# 13_USB30_USB20.net
KiCad netlist of a schematic drawn in Altium Designer
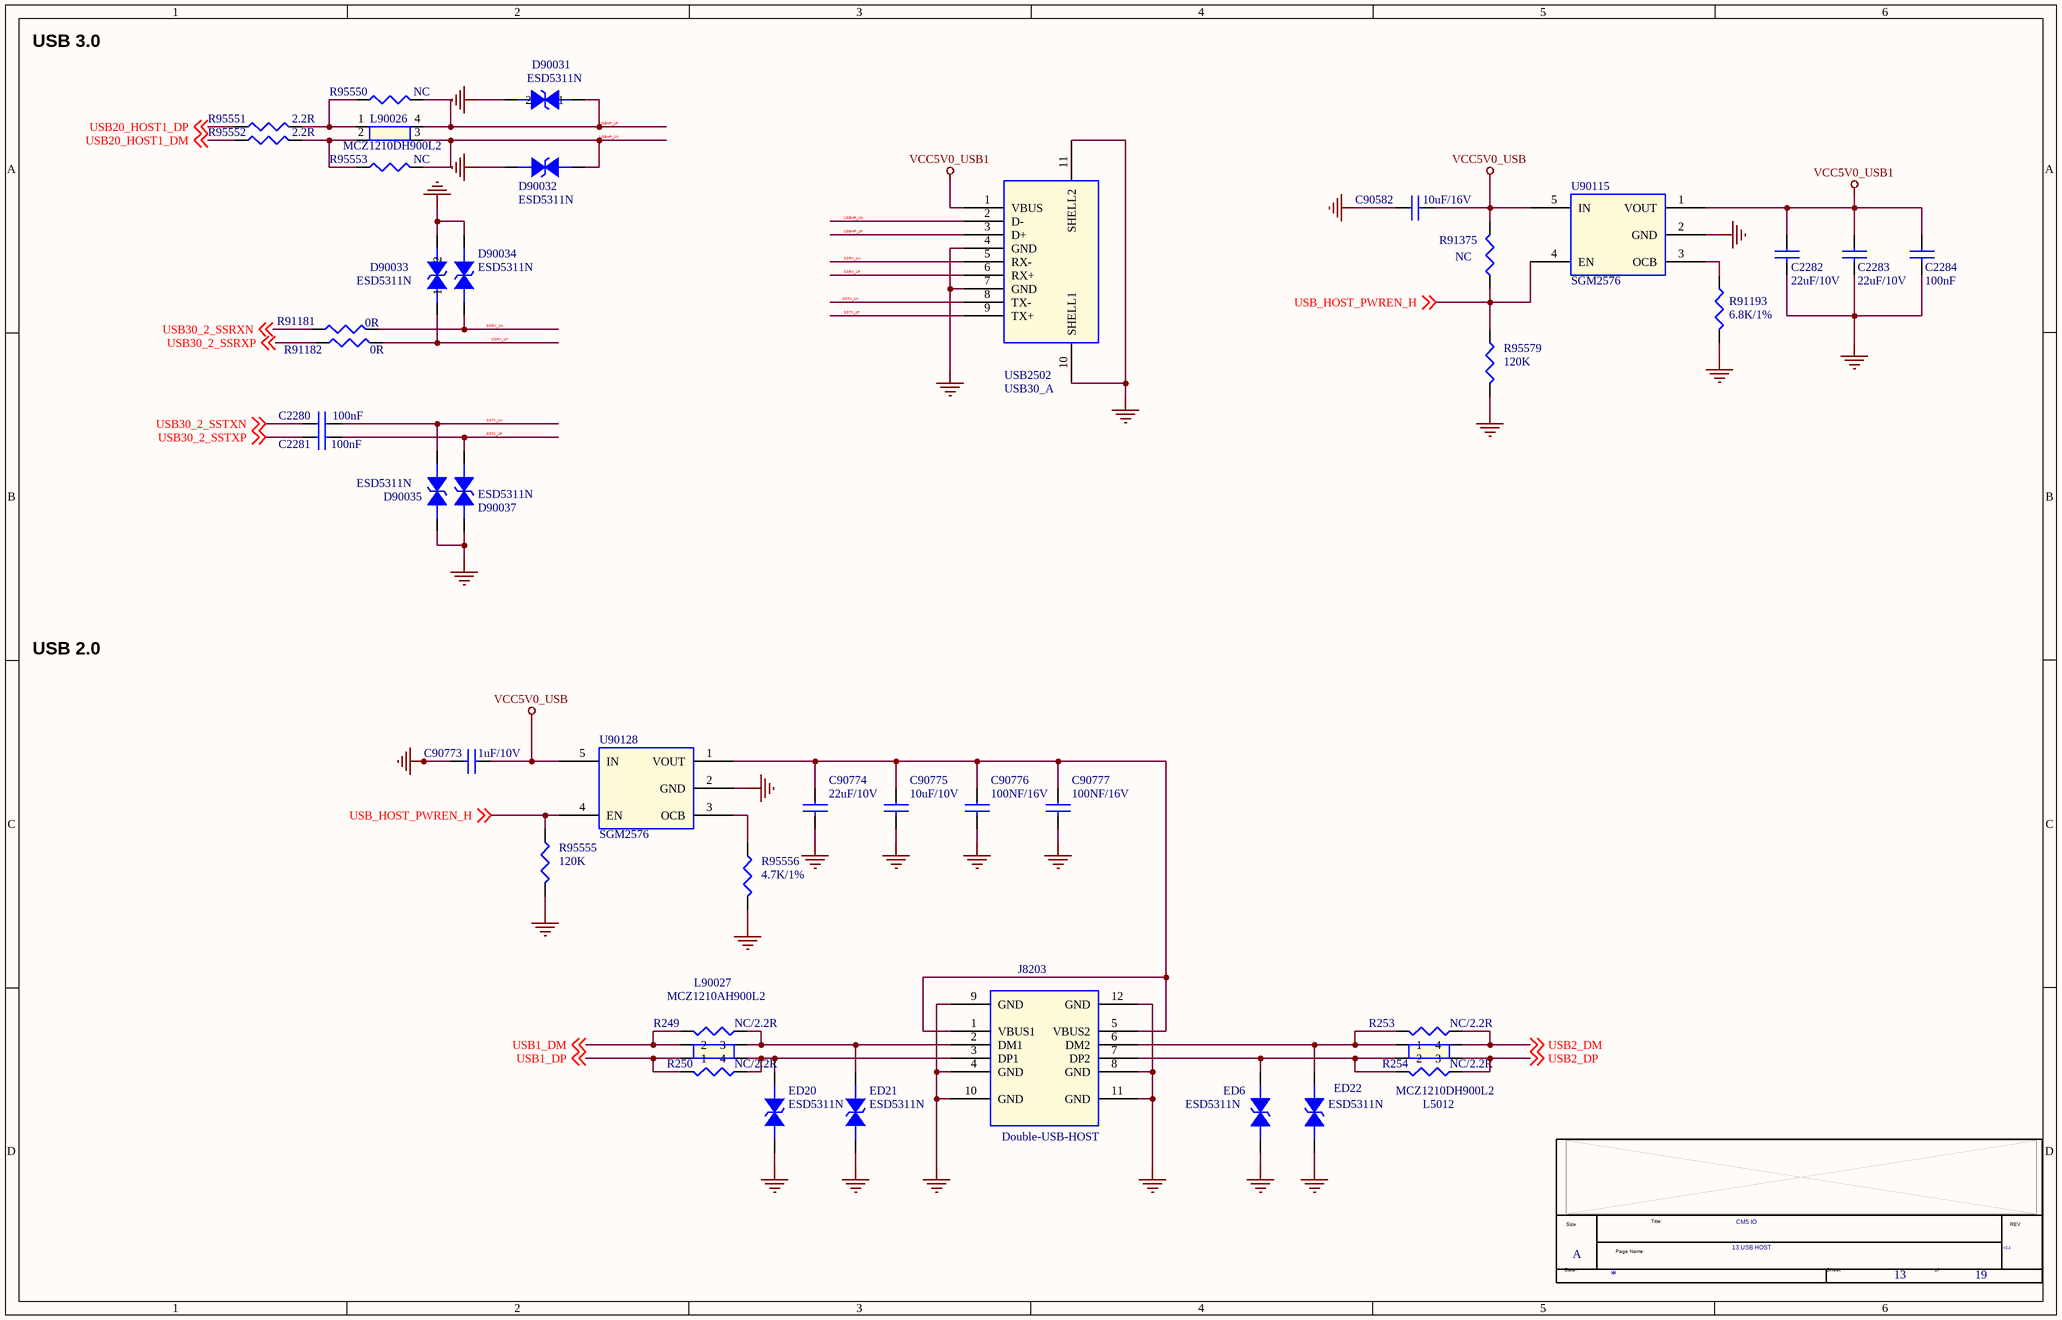
[diagram p0: 13_USB30_USB20.SchDoc]

(export (version "E")
  (design (tool "Eeschema 10.0.6"))
  (components
    (comp (ref "*")
      (value "radxa_1010")
      (fields
        (field (name "DOC") "13.USB HOST")
        (field (name "REVCODE") "V2.2")
        (field (name "TITLE") "CM5 IO")
        (field (name "PAGE SIZE") "A")
        (field (name "PAGE NUMBER") "13")
        (field (name "PAGE COUNT") "19")
      )
      (libsource (lib "*") (part "radxa_1010"))
    )
    (comp (ref "C2280")
      (value "100nF")
      (footprint "C0201")
      (description "cap,100.00nF,+/-10%,10V,X5R,C0201")
      (fields
        (field (name "VOLTAGE") "10V")
        (field (name "MANUFACTURER") "TDK")
        (field (name "CREATED BY") "JJJ")
      )
      (libsource (lib "*") (part "CAP NP_0_Dup1"))
    )
    (comp (ref "C2281")
      (value "100nF")
      (footprint "C0201")
      (description "cap,100.00nF,+/-10%,10V,X5R,C0201")
      (fields
        (field (name "VOLTAGE") "10V")
        (field (name "TOLERANCE") "10%")
        (field (name "CREATED BY") "JJJ")
      )
      (libsource (lib "*") (part "CAP NP_0_Dup1"))
    )
    (comp (ref "C2282")
      (value "22uF/10V")
      (footprint "C0603")
      (description "cap,100.00nF,+/-10%,10V,X5R,C0402")
      (fields
        (field (name "VOLTAGE") "10V")
        (field (name "TOLERANCE") "10%")
        (field (name "CREATED BY") "JJJ")
      )
      (libsource (lib "*") (part "CAP NP_0_Dup1"))
    )
    (comp (ref "C2283")
      (value "22uF/10V")
      (footprint "C0603")
      (description "cap,100.00nF,+/-10%,10V,X5R,C0402")
      (fields
        (field (name "VOLTAGE") "10V")
        (field (name "MANUFACTURER") "TDK")
        (field (name "CREATED BY") "JJJ")
      )
      (libsource (lib "*") (part "CAP NP_0_Dup1"))
    )
    (comp (ref "C2284")
      (value "100nF")
      (footprint "C0201")
      (description "cap,100.00nF,+/-10%,10V,X5R,C0402")
      (fields
        (field (name "VOLTAGE") "10V")
        (field (name "MANUFACTURER") "TDK")
        (field (name "CREATED BY") "JJJ")
      )
      (libsource (lib "*") (part "CAP NP_0_Dup1"))
    )
    (comp (ref "C90582")
      (value "10uF/16V")
      (footprint "C0402")
      (description "0402 ∮20% 10uF X5R 6.3V")
      (libsource (lib "*") (part "C / 10 / uF / 0402_0"))
    )
    (comp (ref "C90773")
      (value "1uF/10V")
      (footprint "C0402")
      (description "cap,1.00uF,+/-10%,10V,X5R,C0402")
      (fields
        (field (name "VOLTAGE") "10V")
        (field (name "MANUFACTURER") "TDK")
        (field (name "CREATED BY") "JJJ")
      )
      (libsource (lib "*") (part "CAP NP_0_Dup2"))
    )
    (comp (ref "C90774")
      (value "22uF/10V")
      (footprint "C0603")
      (description "cap,22.00uF,+/-20%,10V,X5R,C0603")
      (fields
        (field (name "VOLTAGE") "10V")
        (field (name "MANUFACTURER") "TDK")
        (field (name "CREATED BY") "JJJ")
      )
      (libsource (lib "*") (part "CAP NP_0_Dup2"))
    )
    (comp (ref "C90775")
      (value "10uF/10V")
      (footprint "C0603")
      (description "cap,10.00uF,+/-10%,10V,X5R,C0603")
      (fields
        (field (name "VOLTAGE") "10V")
        (field (name "TOLERANCE") "10%")
        (field (name "CREATED BY") "JJJ")
      )
      (libsource (lib "*") (part "CAP NP_0_Dup2"))
    )
    (comp (ref "C90776")
      (value "100NF/16V")
      (footprint "C0402")
      (description "cap,100.00nF,+/-10%,16V,X5R,C0402")
      (fields
        (field (name "VOLTAGE") "16V")
        (field (name "TOLERANCE") "10%")
        (field (name "CREATED BY") "JJJ")
      )
      (libsource (lib "*") (part "CAP NP_0_Dup2"))
    )
    (comp (ref "C90777")
      (value "100NF/16V")
      (footprint "C0402")
      (description "cap,100.00nF,+/-10%,16V,X5R,C0402")
      (fields
        (field (name "VOLTAGE") "16V")
        (field (name "TOLERANCE") "10%")
        (field (name "CREATED BY") "JJJ")
      )
      (libsource (lib "*") (part "CAP NP_0_Dup2"))
    )
    (comp (ref "D90031")
      (value "ESD5311N")
      (footprint "ESD0402")
      (description "1-Line, Bi-directional, Transient Voltage Suppressors.1pF.")
      (fields (field (name "MANUFACTURER") "WillSemi(韦尔半导体)") (field (name "CREATED BY") "JJJ"))
      (libsource (lib "*") (part "DIODE BI_DIR TRIG_0"))
    )
    (comp (ref "D90032")
      (value "ESD5311N")
      (footprint "ESD0402")
      (description "1-Line, Bi-directional, Transient Voltage Suppressors.1pF.")
      (fields (field (name "MANUFACTURER") "WillSemi(韦尔半导体)") (field (name "CREATED BY") "JJJ"))
      (libsource (lib "*") (part "DIODE BI_DIR TRIG_1_Dup1"))
    )
    (comp (ref "D90033")
      (value "ESD5311N")
      (footprint "ESD0402")
      (description "1-Line, Bi-directional, Transient Voltage Suppressors.1pF.")
      (fields (field (name "MANUFACTURER") "WillSemi(韦尔半导体)") (field (name "CREATED BY") "JJJ"))
      (libsource (lib "*") (part "DIODE BI_DIR TRIG_1"))
    )
    (comp (ref "D90034")
      (value "ESD5311N")
      (footprint "ESD0402")
      (description "1-Line, Bi-directional, Transient Voltage Suppressors.1pF.")
      (fields (field (name "MANUFACTURER") "WillSemi(韦尔半导体)") (field (name "CREATED BY") "JJJ"))
      (libsource (lib "*") (part "DIODE BI_DIR TRIG_1_Dup1"))
    )
    (comp (ref "D90035")
      (value "ESD5311N")
      (footprint "ESD0402")
      (description "1-Line, Bi-directional, Transient Voltage Suppressors.1pF.")
      (fields (field (name "MANUFACTURER") "WillSemi(韦尔半导体)") (field (name "CREATED BY") "JJJ"))
      (libsource (lib "*") (part "DIODE BI_DIR TRIG_1_Dup1"))
    )
    (comp (ref "D90037")
      (value "ESD5311N")
      (footprint "ESD0402")
      (description "1-Line, Bi-directional, Transient Voltage Suppressors.1pF.")
      (fields (field (name "MANUFACTURER") "WillSemi(韦尔半导体)") (field (name "CREATED BY") "JJJ"))
      (libsource (lib "*") (part "DIODE BI_DIR TRIG_1_Dup1"))
    )
    (comp (ref "ED6")
      (value "ESD5311N")
      (footprint "ESD0402")
      (description "1-Line, Bi-directional, Transient Voltage Suppressors.1pF.")
      (fields (field (name "MANUFACTURER") "WillSemi(韦尔半导体)") (field (name "CREATED BY") "JJJ"))
      (libsource (lib "*") (part "DIODE BI_DIR TRIG_1_Dup1"))
    )
    (comp (ref "ED20")
      (value "ESD5311N")
      (footprint "ESD0402")
      (description "1-Line, Bi-directional, Transient Voltage Suppressors.1pF.")
      (fields (field (name "MANUFACTURER") "WillSemi(韦尔半导体)") (field (name "CREATED BY") "JJJ"))
      (libsource (lib "*") (part "DIODE BI_DIR TRIG_1_Dup1"))
    )
    (comp (ref "ED21")
      (value "ESD5311N")
      (footprint "ESD0402")
      (description "1-Line, Bi-directional, Transient Voltage Suppressors.1pF.")
      (fields (field (name "MANUFACTURER") "WillSemi(韦尔半导体)") (field (name "CREATED BY") "JJJ"))
      (libsource (lib "*") (part "DIODE BI_DIR TRIG_1_Dup1"))
    )
    (comp (ref "ED22")
      (value "ESD5311N")
      (footprint "ESD0402")
      (description "1-Line, Bi-directional, Transient Voltage Suppressors.1pF.")
      (fields (field (name "MANUFACTURER") "WillSemi(韦尔半导体)") (field (name "CREATED BY") "JJJ"))
      (libsource (lib "*") (part "DIODE BI_DIR TRIG_1_Dup1"))
    )
    (comp (ref "J8203")
      (value "Double-USB-HOST")
      (footprint "USB_DUAL")
      (libsource (lib "*") (part "Double-USB"))
    )
    (comp (ref "L5012")
      (value "MCZ1210DH900L2")
      (footprint "MCZ1210AH900L2")
      (libsource (lib "*") (part "MCZ1210AH900L2_3"))
    )
    (comp (ref "L90026")
      (value "MCZ1210DH900L2")
      (footprint "MCZ1210AH900L2")
      (libsource (lib "*") (part "MCZ1210AH900L2_1_Dup1"))
    )
    (comp (ref "L90027")
      (value "MCZ1210AH900L2")
      (footprint "MCZ1210AH900L2")
      (libsource (lib "") (part "MCZ1210AH900L2_3_1"))
    )
    (comp (ref "R249")
      (value "NC/2.2R")
      (footprint "R0402")
      (description "通用厚膜电阻,2R2,+/-5%,R0402,1/16W.")
      (fields
        (field (name "TOLERANCE") "5%")
        (field (name "MANUFACTURER") "YAGEO")
        (field (name "CREATED BY") "YTL")
      )
      (libsource (lib "*") (part "RESISTOR_1_Dup1"))
    )
    (comp (ref "R250")
      (value "NC/2.2R")
      (footprint "R0402")
      (description "通用厚膜电阻,2R2,+/-5%,R0402,1/16W.")
      (fields
        (field (name "TOLERANCE") "5%")
        (field (name "MANUFACTURER") "YAGEO")
        (field (name "CREATED BY") "YTL")
      )
      (libsource (lib "*") (part "RESISTOR_1_Dup1"))
    )
    (comp (ref "R253")
      (value "NC/2.2R")
      (footprint "R0402")
      (description "通用厚膜电阻,2R2,+/-5%,R0402,1/16W.")
      (fields
        (field (name "TOLERANCE") "5%")
        (field (name "MANUFACTURER") "YAGEO")
        (field (name "CREATED BY") "YTL")
      )
      (libsource (lib "*") (part "RESISTOR_1_Dup1"))
    )
    (comp (ref "R254")
      (value "NC/2.2R")
      (footprint "R0402")
      (description "通用厚膜电阻,2R2,+/-5%,R0402,1/16W.")
      (fields
        (field (name "TOLERANCE") "5%")
        (field (name "MANUFACTURER") "YAGEO")
        (field (name "CREATED BY") "YTL")
      )
      (libsource (lib "*") (part "RESISTOR_1_Dup1"))
    )
    (comp (ref "R91181")
      (value "0R")
      (footprint "R0402")
      (description "通用厚膜电阻,0R,+/-5%,R0201,1/20W.")
      (fields
        (field (name "TOLERANCE") "5%")
        (field (name "MANUFACTURER") "YAGEO")
        (field (name "CREATED BY") "YTL")
      )
      (libsource (lib "*") (part "RESISTOR_0_Dup1"))
    )
    (comp (ref "R91182")
      (value "0R")
      (footprint "R0402")
      (description "通用厚膜电阻,0R,+/-5%,R0201,1/20W.")
      (fields
        (field (name "TOLERANCE") "5%")
        (field (name "MANUFACTURER") "YAGEO")
        (field (name "CREATED BY") "YTL")
      )
      (libsource (lib "*") (part "RESISTOR_0_Dup1"))
    )
    (comp (ref "R91193")
      (value "6.8K/1%")
      (footprint "R0402")
      (description "通用厚膜电阻,4K7,+/-5%,R0402,1/16W.")
      (fields
        (field (name "TOLERANCE") "1%")
        (field (name "MANUFACTURER") "YAGEO")
        (field (name "CREATED BY") "YTL")
      )
      (libsource (lib "*") (part "RESISTOR_0_Dup1"))
    )
    (comp (ref "R91375")
      (value "NC")
      (footprint "R0402")
      (description "Did Not Place.")
      (fields (field (name "TOLERANCE") "0%") (field (name "CREATED BY") "JJJ"))
      (libsource (lib "*") (part "RESISTOR_0_Dup1"))
    )
    (comp (ref "R95550")
      (value "NC")
      (footprint "R0402")
      (description "通用厚膜电阻,2R2,+/-5%,R0402,1/16W.")
      (fields
        (field (name "TOLERANCE") "5%")
        (field (name "MANUFACTURER") "YAGEO")
        (field (name "CREATED BY") "YTL")
      )
      (libsource (lib "*") (part "RESISTOR_0_Dup1"))
    )
    (comp (ref "R95551")
      (value "2.2R")
      (footprint "R0402")
      (description "通用厚膜电阻,2R2,+/-5%,R0402,1/16W.")
      (fields
        (field (name "TOLERANCE") "5%")
        (field (name "MANUFACTURER") "YAGEO")
        (field (name "CREATED BY") "YTL")
      )
      (libsource (lib "*") (part "RESISTOR_0_Dup1"))
    )
    (comp (ref "R95552")
      (value "2.2R")
      (footprint "R0402")
      (description "通用厚膜电阻,2R2,+/-5%,R0402,1/16W.")
      (fields
        (field (name "TOLERANCE") "5%")
        (field (name "MANUFACTURER") "YAGEO")
        (field (name "CREATED BY") "YTL")
      )
      (libsource (lib "*") (part "RESISTOR_0_Dup1"))
    )
    (comp (ref "R95553")
      (value "NC")
      (footprint "R0402")
      (description "通用厚膜电阻,2R2,+/-5%,R0402,1/16W.")
      (fields
        (field (name "TOLERANCE") "5%")
        (field (name "MANUFACTURER") "YAGEO")
        (field (name "CREATED BY") "YTL")
      )
      (libsource (lib "*") (part "RESISTOR_0_Dup1"))
    )
    (comp (ref "R95555")
      (value "120K")
      (footprint "R0402")
      (description "通用厚膜电阻,100K,+/-5%,R0402,1/16W.")
      (fields
        (field (name "TOLERANCE") "5%")
        (field (name "MANUFACTURER") "YAGEO")
        (field (name "CREATED BY") "YTL")
      )
      (libsource (lib "*") (part "RESISTOR_1_Dup1"))
    )
    (comp (ref "R95556")
      (value "4.7K/1%")
      (footprint "R0402")
      (description "通用厚膜电阻,10K,+/-1%,R0402,1/16W.")
      (fields
        (field (name "TOLERANCE") "1%")
        (field (name "MANUFACTURER") "YAGEO")
        (field (name "CREATED BY") "YTL")
      )
      (libsource (lib "*") (part "RESISTOR_1_Dup1"))
    )
    (comp (ref "R95579")
      (value "120K")
      (footprint "R0402")
      (description "通用厚膜电阻,100K,+/-5%,R0402,1/16W.")
      (fields
        (field (name "TOLERANCE") "5%")
        (field (name "MANUFACTURER") "YAGEO")
        (field (name "CREATED BY") "YTL")
      )
      (libsource (lib "*") (part "RESISTOR_1_Dup1"))
    )
    (comp (ref "U90115")
      (value "SGM2576")
      (footprint "SOT_23_5")
      (description "Low Loss Power Distribution Switch")
      (fields (field (name "MANUFACTURER") "Silergy（矽力杰）") (field (name "CREATED BY") "JJJ"))
      (libsource (lib "*") (part "SWITCH_SY6280"))
    )
    (comp (ref "U90128")
      (value "SGM2576")
      (footprint "SOT_23_5")
      (description "Low Loss Power Distribution Switch")
      (fields (field (name "MANUFACTURER") "Silergy（矽力杰）") (field (name "CREATED BY") "JJJ"))
      (libsource (lib "*") (part "SWITCH_SY6280"))
    )
    (comp (ref "USB2502")
      (value "USB30_A")
      (footprint "USB30")
      (description "A型USB3.0座，卧式，插焊")
      (fields (field (name "MANUFACTURER") "旺科达") (field (name "CREATED BY") "JJJ"))
      (libsource (lib "*") (part "USB30_TYPE_A"))
    )
  )
  (nets
    (net (code "1") (name "/SSRX_1N") (class "Default")
      (node (ref "D90034") (pin "1") (pinfunction "1_1") (pintype "passive"))
      (node (ref "R91181") (pin "2") (pinfunction "2_2") (pintype "passive"))
      (node (ref "USB2502") (pin "5") (pinfunction "RX-_5") (pintype "passive"))
    )
    (net (code "2") (name "/SSRX_1P") (class "Default")
      (node (ref "D90033") (pin "1") (pinfunction "1_1") (pintype "passive"))
      (node (ref "R91182") (pin "2") (pinfunction "2_2") (pintype "passive"))
      (node (ref "USB2502") (pin "6") (pinfunction "RX+_6") (pintype "passive"))
    )
    (net (code "3") (name "/SSTX_1N") (class "Default")
      (node (ref "C2280") (pin "2") (pinfunction "2_2") (pintype "passive"))
      (node (ref "D90035") (pin "1") (pinfunction "1_1") (pintype "passive"))
      (node (ref "USB2502") (pin "8") (pinfunction "TX-_8") (pintype "passive"))
    )
    (net (code "4") (name "/SSTX_1P") (class "Default")
      (node (ref "C2281") (pin "2") (pinfunction "2_2") (pintype "passive"))
      (node (ref "D90037") (pin "1") (pinfunction "1_1") (pintype "passive"))
      (node (ref "USB2502") (pin "9") (pinfunction "TX+_9") (pintype "passive"))
    )
    (net (code "5") (name "/USBHP_1N") (class "Default")
      (node (ref "D90032") (pin "1") (pinfunction "1_1") (pintype "passive"))
      (node (ref "L90026") (pin "3") (pinfunction "3_3") (pintype "passive"))
      (node (ref "R95553") (pin "2") (pinfunction "2_2") (pintype "passive"))
      (node (ref "USB2502") (pin "2") (pinfunction "D-_2") (pintype "passive"))
    )
    (net (code "6") (name "/USBHP_1P") (class "Default")
      (node (ref "D90031") (pin "1") (pinfunction "1_1") (pintype "passive"))
      (node (ref "L90026") (pin "4") (pinfunction "4_4") (pintype "passive"))
      (node (ref "R95550") (pin "2") (pinfunction "2_2") (pintype "passive"))
      (node (ref "USB2502") (pin "3") (pinfunction "D+_3") (pintype "passive"))
    )
    (net (code "7") (name "GND") (class "Default")
      (node (ref "C2282") (pin "2") (pinfunction "2_2") (pintype "passive"))
      (node (ref "C2283") (pin "2") (pinfunction "2_2") (pintype "passive"))
      (node (ref "C2284") (pin "2") (pinfunction "2_2") (pintype "passive"))
      (node (ref "C90582") (pin "1") (pinfunction "1_1") (pintype "passive"))
      (node (ref "C90773") (pin "2") (pinfunction "2_2") (pintype "passive"))
      (node (ref "C90774") (pin "2") (pinfunction "2_2") (pintype "passive"))
      (node (ref "C90775") (pin "2") (pinfunction "2_2") (pintype "passive"))
      (node (ref "C90776") (pin "2") (pinfunction "2_2") (pintype "passive"))
      (node (ref "C90777") (pin "2") (pinfunction "2_2") (pintype "passive"))
      (node (ref "D90031") (pin "2") (pinfunction "2_2") (pintype "passive"))
      (node (ref "D90032") (pin "2") (pinfunction "2_2") (pintype "passive"))
      (node (ref "D90033") (pin "2") (pinfunction "2_2") (pintype "passive"))
      (node (ref "D90034") (pin "2") (pinfunction "2_2") (pintype "passive"))
      (node (ref "D90035") (pin "2") (pinfunction "2_2") (pintype "passive"))
      (node (ref "D90037") (pin "2") (pinfunction "2_2") (pintype "passive"))
      (node (ref "ED20") (pin "2") (pinfunction "2_2") (pintype "passive"))
      (node (ref "ED21") (pin "2") (pinfunction "2_2") (pintype "passive"))
      (node (ref "ED22") (pin "2") (pinfunction "2_2") (pintype "passive"))
      (node (ref "ED6") (pin "2") (pinfunction "2_2") (pintype "passive"))
      (node (ref "J8203") (pin "10") (pinfunction "GND_10") (pintype "passive"))
      (node (ref "J8203") (pin "11") (pinfunction "GND_11") (pintype "passive"))
      (node (ref "J8203") (pin "12") (pinfunction "GND_12") (pintype "passive"))
      (node (ref "J8203") (pin "4") (pinfunction "GND_4") (pintype "passive"))
      (node (ref "J8203") (pin "8") (pinfunction "GND_8") (pintype "passive"))
      (node (ref "J8203") (pin "9") (pinfunction "GND_9") (pintype "passive"))
      (node (ref "R91193") (pin "2") (pinfunction "2_2") (pintype "passive"))
      (node (ref "R95555") (pin "2") (pinfunction "2_2") (pintype "passive"))
      (node (ref "R95556") (pin "2") (pinfunction "2_2") (pintype "passive"))
      (node (ref "R95579") (pin "2") (pinfunction "2_2") (pintype "passive"))
      (node (ref "U90115") (pin "2") (pinfunction "GND_2") (pintype "passive"))
      (node (ref "U90128") (pin "2") (pinfunction "GND_2") (pintype "passive"))
      (node (ref "USB2502") (pin "10") (pinfunction "SHELL1_10") (pintype "passive"))
      (node (ref "USB2502") (pin "11") (pinfunction "SHELL2_11") (pintype "passive"))
      (node (ref "USB2502") (pin "4") (pinfunction "GND_4") (pintype "power_in"))
      (node (ref "USB2502") (pin "7") (pinfunction "GND_7") (pintype "power_in"))
    )
    (net (code "8") (name "Net-(J8203-DM1)") (class "Default")
      (node (ref "ED21") (pin "1") (pinfunction "1_1") (pintype "passive"))
      (node (ref "J8203") (pin "2") (pinfunction "DM1_2") (pintype "passive"))
      (node (ref "L90027") (pin "3") (pinfunction "3_3") (pintype "passive"))
      (node (ref "R249") (pin "1") (pinfunction "1_1") (pintype "passive"))
    )
    (net (code "9") (name "Net-(J8203-DM2)") (class "Default")
      (node (ref "ED22") (pin "1") (pinfunction "1_1") (pintype "passive"))
      (node (ref "J8203") (pin "6") (pinfunction "DM2_6") (pintype "passive"))
      (node (ref "L5012") (pin "1") (pinfunction "1_1") (pintype "passive"))
      (node (ref "R253") (pin "2") (pinfunction "2_2") (pintype "passive"))
    )
    (net (code "10") (name "Net-(J8203-DP1)") (class "Default")
      (node (ref "ED20") (pin "1") (pinfunction "1_1") (pintype "passive"))
      (node (ref "J8203") (pin "3") (pinfunction "DP1_3") (pintype "passive"))
      (node (ref "L90027") (pin "4") (pinfunction "4_4") (pintype "passive"))
      (node (ref "R250") (pin "1") (pinfunction "1_1") (pintype "passive"))
    )
    (net (code "11") (name "Net-(J8203-DP2)") (class "Default")
      (node (ref "ED6") (pin "1") (pinfunction "1_1") (pintype "passive"))
      (node (ref "J8203") (pin "7") (pinfunction "DP2_7") (pintype "passive"))
      (node (ref "L5012") (pin "2") (pinfunction "2_2") (pintype "passive"))
      (node (ref "R254") (pin "2") (pinfunction "2_2") (pintype "passive"))
    )
    (net (code "12") (name "Net-(J8203-VBUS1)") (class "Default")
      (node (ref "C90774") (pin "1") (pinfunction "1_1") (pintype "passive"))
      (node (ref "C90775") (pin "1") (pinfunction "1_1") (pintype "passive"))
      (node (ref "C90776") (pin "1") (pinfunction "1_1") (pintype "passive"))
      (node (ref "C90777") (pin "1") (pinfunction "1_1") (pintype "passive"))
      (node (ref "J8203") (pin "1") (pinfunction "VBUS1_1") (pintype "passive"))
      (node (ref "J8203") (pin "5") (pinfunction "VBUS2_5") (pintype "passive"))
      (node (ref "U90128") (pin "1") (pinfunction "VOUT_1") (pintype "passive"))
    )
    (net (code "13") (name "Net-(L90026-Pad1)") (class "Default")
      (node (ref "L90026") (pin "1") (pinfunction "1_1") (pintype "passive"))
      (node (ref "R95550") (pin "1") (pinfunction "1_1") (pintype "passive"))
      (node (ref "R95551") (pin "2") (pinfunction "2_2") (pintype "passive"))
    )
    (net (code "14") (name "Net-(L90026-Pad2)") (class "Default")
      (node (ref "L90026") (pin "2") (pinfunction "2_2") (pintype "passive"))
      (node (ref "R95552") (pin "2") (pinfunction "2_2") (pintype "passive"))
      (node (ref "R95553") (pin "1") (pinfunction "1_1") (pintype "passive"))
    )
    (net (code "15") (name "Net-(U90115-OCB)") (class "Default")
      (node (ref "R91193") (pin "1") (pinfunction "1_1") (pintype "passive"))
      (node (ref "U90115") (pin "3") (pinfunction "OCB_3") (pintype "passive"))
    )
    (net (code "16") (name "Net-(U90128-OCB)") (class "Default")
      (node (ref "R95556") (pin "1") (pinfunction "1_1") (pintype "passive"))
      (node (ref "U90128") (pin "3") (pinfunction "OCB_3") (pintype "passive"))
    )
    (net (code "17") (name "USB1_DM") (class "Default")
      (node (ref "L90027") (pin "2") (pinfunction "2_2") (pintype "passive"))
      (node (ref "R249") (pin "2") (pinfunction "2_2") (pintype "passive"))
    )
    (net (code "18") (name "USB1_DP") (class "Default")
      (node (ref "L90027") (pin "1") (pinfunction "1_1") (pintype "passive"))
      (node (ref "R250") (pin "2") (pinfunction "2_2") (pintype "passive"))
    )
    (net (code "19") (name "USB2_DM") (class "Default")
      (node (ref "L5012") (pin "4") (pinfunction "4_4") (pintype "passive"))
      (node (ref "R253") (pin "1") (pinfunction "1_1") (pintype "passive"))
    )
    (net (code "20") (name "USB2_DP") (class "Default")
      (node (ref "L5012") (pin "3") (pinfunction "3_3") (pintype "passive"))
      (node (ref "R254") (pin "1") (pinfunction "1_1") (pintype "passive"))
    )
    (net (code "21") (name "USB20_HOST1_DM") (class "Default")
      (node (ref "R95552") (pin "1") (pinfunction "1_1") (pintype "passive"))
    )
    (net (code "22") (name "USB20_HOST1_DP") (class "Default")
      (node (ref "R95551") (pin "1") (pinfunction "1_1") (pintype "passive"))
    )
    (net (code "23") (name "USB30_2_SSRXN") (class "Default")
      (node (ref "R91181") (pin "1") (pinfunction "1_1") (pintype "passive"))
    )
    (net (code "24") (name "USB30_2_SSRXP") (class "Default")
      (node (ref "R91182") (pin "1") (pinfunction "1_1") (pintype "passive"))
    )
    (net (code "25") (name "USB30_2_SSTXN") (class "Default")
      (node (ref "C2280") (pin "1") (pinfunction "1_1") (pintype "passive"))
    )
    (net (code "26") (name "USB30_2_SSTXP") (class "Default")
      (node (ref "C2281") (pin "1") (pinfunction "1_1") (pintype "passive"))
    )
    (net (code "27") (name "USB_HOST_PWREN_H") (class "Default")
      (node (ref "R91375") (pin "2") (pinfunction "2_2") (pintype "passive"))
      (node (ref "R95555") (pin "1") (pinfunction "1_1") (pintype "passive"))
      (node (ref "R95579") (pin "1") (pinfunction "1_1") (pintype "passive"))
      (node (ref "U90115") (pin "4") (pinfunction "EN_4") (pintype "passive"))
      (node (ref "U90128") (pin "4") (pinfunction "EN_4") (pintype "passive"))
    )
    (net (code "28") (name "VCC5V0_USB") (class "Default")
      (node (ref "C90582") (pin "2") (pinfunction "2_2") (pintype "passive"))
      (node (ref "C90773") (pin "1") (pinfunction "1_1") (pintype "passive"))
      (node (ref "R91375") (pin "1") (pinfunction "1_1") (pintype "passive"))
      (node (ref "U90115") (pin "5") (pinfunction "IN_5") (pintype "passive"))
      (node (ref "U90128") (pin "5") (pinfunction "IN_5") (pintype "passive"))
    )
    (net (code "29") (name "VCC5V0_USB1") (class "Default")
      (node (ref "C2282") (pin "1") (pinfunction "1_1") (pintype "passive"))
      (node (ref "C2283") (pin "1") (pinfunction "1_1") (pintype "passive"))
      (node (ref "C2284") (pin "1") (pinfunction "1_1") (pintype "passive"))
      (node (ref "U90115") (pin "1") (pinfunction "VOUT_1") (pintype "passive"))
      (node (ref "USB2502") (pin "1") (pinfunction "VBUS_1") (pintype "power_in"))
    )
  )
)
